# SmartWatch-V2-Power.net
KiCad netlist of a schematic drawn in Altium Designer
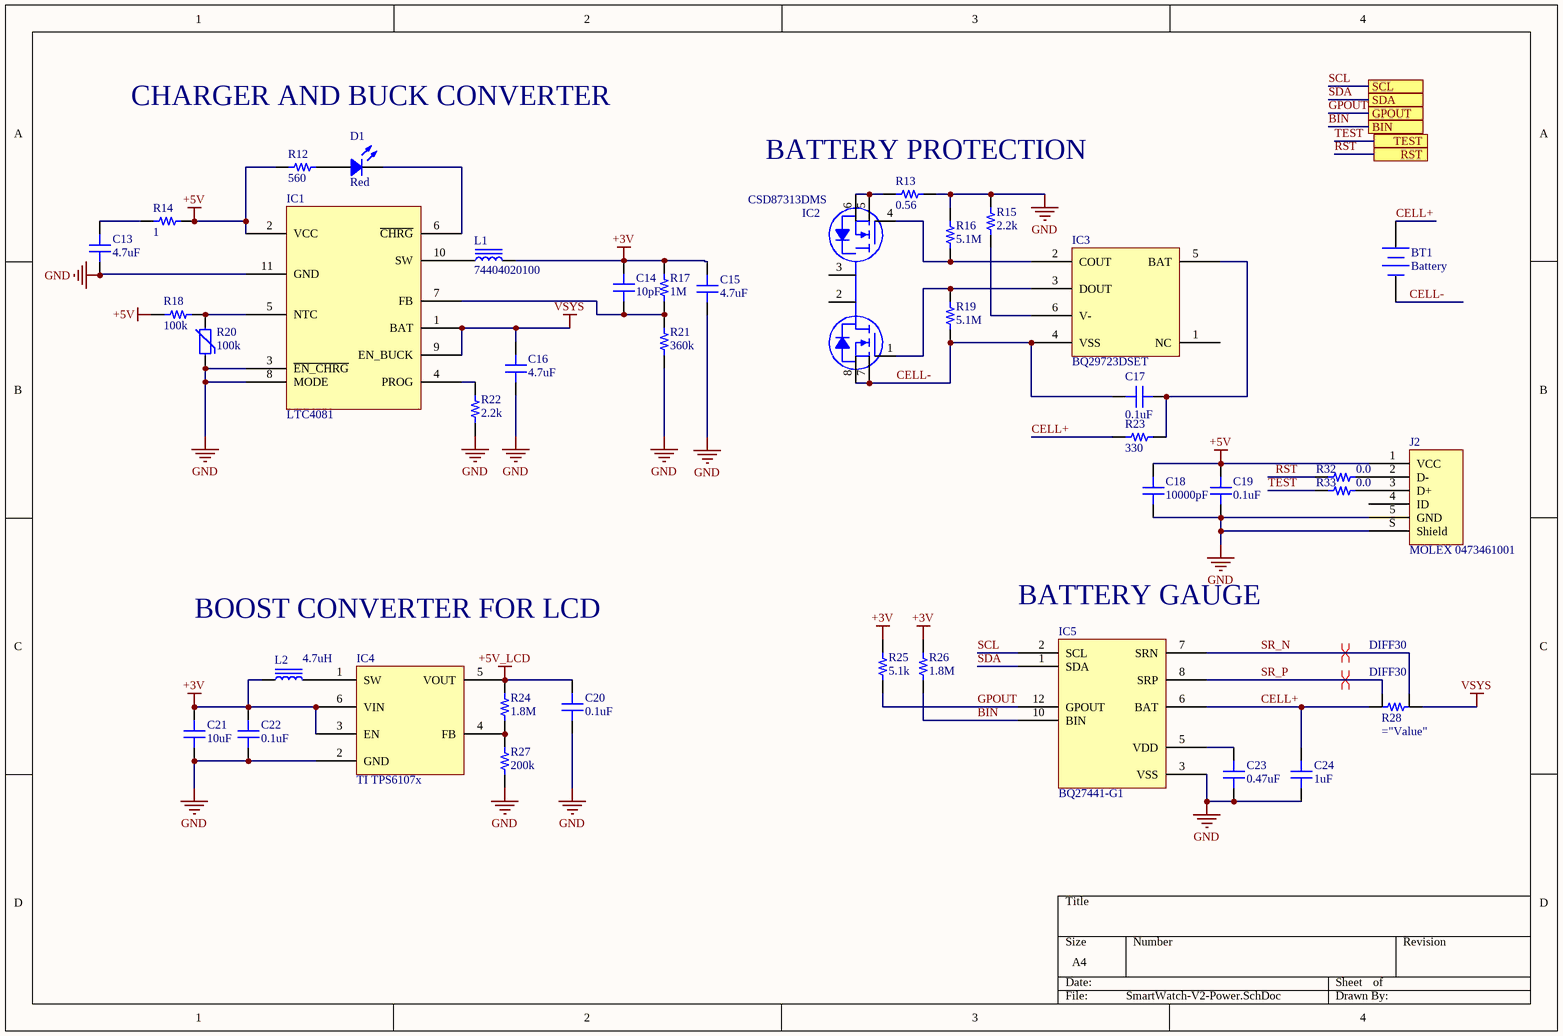
[diagram p0: SmartWatch-V2-Power.SchDoc]

(export (version "E")
  (design (tool "Eeschema 10.0.6"))
  (components
    (comp (ref "BT1")
      (value "Battery")
      (footprint "BAT-2")
      (description "Multicell Battery")
      (fields (field (name "PUBLISHER") "Altium Limited"))
      (libsource (lib "Miscellaneous Devices") (part "Battery"))
    )
    (comp (ref "C13")
      (value "4.7uF")
      (footprint "CAP 0402/1005")
      (description "CAP CER 4.7UF 4V X5R 0402")
      (fields (field (name "PART NUMBER") "CC0402MRX5R4BB475") (field (name "MANUFACTURER") "Yageo"))
      (libsource (lib "Celestial Library Database") (part "Capacitor"))
    )
    (comp (ref "C14")
      (value "10pF")
      (footprint "CAP 0402/1005")
      (description "CAP CER 10PF 50V C0G 0402")
      (fields
        (field (name "PART NUMBER") "C1005C0G1H100D050BA")
        (field (name "MANUFACTURER") "TDK Corporation")
      )
      (libsource (lib "Celestial Library Database") (part "Capacitor"))
    )
    (comp (ref "C15")
      (value "4.7uF")
      (footprint "CAP 0402/1005")
      (description "CAP CER 4.7UF 4V X5R 0402")
      (fields (field (name "PART NUMBER") "CC0402MRX5R4BB475") (field (name "MANUFACTURER") "Yageo"))
      (libsource (lib "Celestial Library Database") (part "Capacitor"))
    )
    (comp (ref "C16")
      (value "4.7uF")
      (footprint "CAP 0402/1005")
      (description "CAP CER 4.7UF 4V X5R 0402")
      (fields (field (name "PART NUMBER") "CC0402MRX5R4BB475") (field (name "MANUFACTURER") "Yageo"))
      (libsource (lib "Celestial Library Database") (part "Capacitor"))
    )
    (comp (ref "C17")
      (value "0.1uF")
      (footprint "CAP 0402/1005")
      (description "CAP CER 0.1UF 25V X7R 0402")
      (fields
        (field (name "PART NUMBER") "C1005X7R1E104K050BB")
        (field (name "MANUFACTURER") "TDK Corporation")
      )
      (libsource (lib "Celestial Library Database") (part "Capacitor"))
    )
    (comp (ref "C18")
      (value "10000pF")
      (footprint "CAP 0603/1608")
      (description "CAP CER 10000PF 100V X7R 0603")
      (fields
        (field (name "PART NUMBER") "C1608X7R2A103K080AA")
        (field (name "MANUFACTURER") "TDK Corporation")
      )
      (libsource (lib "Celestial Library Database") (part "Capacitor"))
    )
    (comp (ref "C19")
      (value "0.1uF")
      (footprint "CAP 0402/1005")
      (description "CAP CER 0.1UF 25V X7R 0402")
      (fields
        (field (name "PART NUMBER") "C1005X7R1E104K050BB")
        (field (name "MANUFACTURER") "TDK Corporation")
      )
      (libsource (lib "Celestial Library Database") (part "Capacitor"))
    )
    (comp (ref "C20")
      (value "0.1uF")
      (footprint "CAP 0402/1005")
      (description "CAP CER 0.1UF 25V X7R 0402")
      (fields
        (field (name "PART NUMBER") "C1005X7R1E104K050BB")
        (field (name "MANUFACTURER") "TDK Corporation")
      )
      (libsource (lib "Celestial Library Database") (part "Capacitor"))
    )
    (comp (ref "C21")
      (value "10uF")
      (footprint "CAP 0402/1005")
      (description "CAP CER 10UF 6.3V X5R 0402")
      (fields
        (field (name "PART NUMBER") "C1005X5R0J106M050BC")
        (field (name "MANUFACTURER") "TDK Corporation")
      )
      (libsource (lib "Celestial Library Database") (part "Capacitor"))
    )
    (comp (ref "C22")
      (value "0.1uF")
      (footprint "CAP 0402/1005")
      (description "CAP CER 0.1UF 25V X7R 0402")
      (fields
        (field (name "PART NUMBER") "C1005X7R1E104K050BB")
        (field (name "MANUFACTURER") "TDK Corporation")
      )
      (libsource (lib "Celestial Library Database") (part "Capacitor"))
    )
    (comp (ref "C23")
      (value "0.47uF")
      (footprint "CAP 0402/1005")
      (description "CAP CER 0.47UF 10V X5R 0402")
      (fields
        (field (name "PART NUMBER") "GRM155R61A474KE15D")
        (field (name "MANUFACTURER") "Murata Electronics North America")
      )
      (libsource (lib "Celestial Library Database") (part "Capacitor"))
    )
    (comp (ref "C24")
      (value "1uF")
      (footprint "CAP 0402/1005")
      (description "CAP CER 1UF 4V X7R 0402")
      (fields
        (field (name "PART NUMBER") "GRM155R70G105KA12D")
        (field (name "MANUFACTURER") "Murata Electronics North America")
      )
      (libsource (lib "Celestial Library Database") (part "Capacitor"))
    )
    (comp (ref "D1")
      (value "Red")
      (footprint "LED 0603/1608 RED")
      (description "LED RED DIFFUSED 0603 SMD")
      (fields (field (name "PART NUMBER") "5975112407F") (field (name "MANUFACTURER") "Dialight"))
      (libsource (lib "Celestial Library Database") (part "LED"))
    )
    (comp (ref "IC1")
      (value "LTC4081")
      (footprint "LT DFN-10 3mmx3mm DD")
      (description "IC BATTA CHRGR LI-ON with BUCK 10 DFN")
      (fields (field (name "MANUFACTURER") "Linear Technology"))
      (libsource (lib "Celestial Library Database") (part "LT LTC4081"))
    )
    (comp (ref "IC2")
      (value "CSD87313DMS")
      (footprint "TI WSON-8 3.3x3.3mm")
      (description "MOSFET 2 N-CHANNEL 30V 8WSON")
      (fields (field (name "MANUFACTURER") "Texas Instruments"))
      (libsource (lib "Celestial Library Database") (part "TI CSD87313DMS"))
    )
    (comp (ref "IC3")
      (value "BQ29723DSET")
      (footprint "TI WSON-6")
      (description "IC LITHIUM BATT PROTECT 6WSON")
      (fields (field (name "MANUFACTURER") "Texas Instruments"))
      (libsource (lib "Celestial Library Database") (part "TI BQ297x"))
    )
    (comp (ref "IC4")
      (value "TI TPS6107x")
      (footprint "TI SOT-23-6 DDC")
      (description "IC REG BOOST ADJ 455MA SYNC SOT6")
      (fields (field (name "MANUFACTURER") "Texas Instruments"))
      (libsource (lib "Celestial Library Database") (part "TI TPS6107x"))
    )
    (comp (ref "IC5")
      (value "BQ27441-G1")
      (footprint "TI VSON-12 2.5x4mm")
      (description "IC BATT FUEL GAUGE LI-ION 12SON")
      (fields (field (name "MANUFACTURER") "Texas Instruments"))
      (libsource (lib "Celestial Library Database") (part "TI BQ27441-G1"))
    )
    (comp (ref "J2")
      (value "MOLEX 0473461001")
      (footprint "MOLEX 0473461001")
      (description "CONN USB B SINGLE SMT HORIZ CONNECTOR")
      (fields (field (name "MANUFACTURER") "Molex"))
      (libsource (lib "Celestial Library Database") (part "USB 2.0 Type B Micro"))
    )
    (comp (ref "L1")
      (value "74404020100")
      (footprint "TDK VLS201612CX")
      (fields
        (field (name "PART NUMBER") "VLS201610CX-100M")
        (field (name "MANUFACTURER") "TDK Corporation")
        (field (name "TOLERANCE") "20%")
      )
      (libsource (lib "Celestial Library Database") (part "Inductor"))
    )
    (comp (ref "L2")
      (value "4.7uH")
      (footprint "TDK VLS201612CX")
      (description "FIXED IND 4.7UH 1.12A 252 MOHM")
      (fields (field (name "PART NUMBER") "VLS201612CX-4R7M") (field (name "MANUFACTURER") "TDK Corporation"))
      (libsource (lib "Celestial Library Database") (part "Inductor"))
    )
    (comp (ref "R12")
      (value "560")
      (footprint "RES 0402/1005")
      (description "RES SMD 560 OHM 0.1% 1/16W 0402")
      (fields
        (field (name "PART NUMBER") "ERA-2APB561X")
        (field (name "MANUFACTURER") "Panasonic Electronic Components")
      )
      (libsource (lib "Celestial Library Database") (part "Resistor"))
    )
    (comp (ref "R13")
      (value "0.56")
      (footprint "RES 0603/1608")
      (description "RES SMD 0.56 OHM 5% 1/4W 0603")
      (fields
        (field (name "PART NUMBER") "ERJ-3BQJR56V")
        (field (name "MANUFACTURER") "Panasonic Electronic Components")
      )
      (libsource (lib "Celestial Library Database") (part "Resistor"))
    )
    (comp (ref "R14")
      (value "1")
      (footprint "RES 0402/1005")
      (description "RES SMD 1 OHM 5% 1/16W 0402")
      (fields (field (name "PART NUMBER") "RC0402JR-071RL") (field (name "MANUFACTURER") "Yageo"))
      (libsource (lib "Celestial Library Database") (part "Resistor"))
    )
    (comp (ref "R15")
      (value "2.2k")
      (footprint "RES 0402/1005")
      (description "RES SMD 2.2K OHM 0.1% 1/16W 0402")
      (fields
        (field (name "PART NUMBER") "ERA-2AEB222X")
        (field (name "MANUFACTURER") "Panasonic Electronic Components")
      )
      (libsource (lib "Celestial Library Database") (part "Resistor"))
    )
    (comp (ref "R16")
      (value "5.1M")
      (footprint "RES 0402/1005")
      (description "RES SMD 5.1M OHM 5% 1/10W 0402")
      (fields
        (field (name "PART NUMBER") "ERJ-2GEJ515X")
        (field (name "MANUFACTURER") "Panasonic Electronic Components")
      )
      (libsource (lib "Celestial Library Database") (part "Resistor"))
    )
    (comp (ref "R17")
      (value "1M")
      (footprint "RES 0402/1005")
      (description "RES SMD 1M OHM 5% 1/10W 0402")
      (fields
        (field (name "PART NUMBER") "ERJ-2GEJ105X")
        (field (name "MANUFACTURER") "Panasonic Electronic Components")
      )
      (libsource (lib "Celestial Library Database") (part "Resistor"))
    )
    (comp (ref "R18")
      (value "100k")
      (footprint "RES 0402/1005")
      (description "RES SMD 100K OHM 0.5% 1/16W 0402")
      (fields
        (field (name "PART NUMBER") "ERA-2AED104X")
        (field (name "MANUFACTURER") "Panasonic Electronic Components")
      )
      (libsource (lib "Celestial Library Database") (part "Resistor"))
    )
    (comp (ref "R19")
      (value "5.1M")
      (footprint "RES 0402/1005")
      (description "RES SMD 5.1M OHM 5% 1/10W 0402")
      (fields
        (field (name "PART NUMBER") "ERJ-2GEJ515X")
        (field (name "MANUFACTURER") "Panasonic Electronic Components")
      )
      (libsource (lib "Celestial Library Database") (part "Resistor"))
    )
    (comp (ref "R20")
      (value "~")
      (footprint "FER 0603/1608")
      (description "THERMISTOR NTC 100K OHM 5% 0603")
      (fields
        (field (name "PART NUMBER") "ABNTC-0603-104J-4250F-T")
        (field (name "RESISTANCE IN OHMS @ 25C") "100k")
        (field (name "MANUFACTURER") "Abracon LLC")
      )
      (libsource (lib "Celestial Library Database") (part "Thermistor"))
    )
    (comp (ref "R21")
      (value "360k")
      (footprint "RES 0402/1005")
      (description "RES SMD 360K OHM 5% 1/10W 0402")
      (fields
        (field (name "PART NUMBER") "ERJ-2GEJ364X")
        (field (name "MANUFACTURER") "Panasonic Electronic Components")
      )
      (libsource (lib "Celestial Library Database") (part "Resistor"))
    )
    (comp (ref "R22")
      (value "2.2k")
      (footprint "RES 0402/1005")
      (description "RES SMD 2.2K OHM 0.1% 1/16W 0402")
      (fields
        (field (name "PART NUMBER") "ERA-2AEB222X")
        (field (name "MANUFACTURER") "Panasonic Electronic Components")
      )
      (libsource (lib "Celestial Library Database") (part "Resistor"))
    )
    (comp (ref "R23")
      (value "330")
      (footprint "RES 0402/1005")
      (description "RES SMD 330 OHM 0.5% 1/16W 0402")
      (fields
        (field (name "PART NUMBER") "ERA-2AED331X")
        (field (name "MANUFACTURER") "Panasonic Electronic Components")
      )
      (libsource (lib "Celestial Library Database") (part "Resistor"))
    )
    (comp (ref "R24")
      (value "1.8M")
      (footprint "RES 0603/1608")
      (description "RES SMD 1.8M OHM 5% 1/10W 0603")
      (fields
        (field (name "PART NUMBER") "ERJ-3GEYJ185V")
        (field (name "MANUFACTURER") "Panasonic Electronic Components")
      )
      (libsource (lib "Celestial Library Database") (part "Resistor"))
    )
    (comp (ref "R25")
      (value "5.1k")
      (footprint "RES 0402/1005")
      (description "RES SMD 5.1K OHM 0.5% 1/16W 0402")
      (fields
        (field (name "PART NUMBER") "ERA-2AED512X")
        (field (name "MANUFACTURER") "Panasonic Electronic Components")
      )
      (libsource (lib "Celestial Library Database") (part "Resistor"))
    )
    (comp (ref "R26")
      (value "1.8M")
      (footprint "RES 0402/1005")
      (description "RES SMD 1.8M OHM 5% 1/10W 0402")
      (fields
        (field (name "PART NUMBER") "ERJ-2GEJ185X")
        (field (name "MANUFACTURER") "Panasonic Electronic Components")
      )
      (libsource (lib "Celestial Library Database") (part "Resistor"))
    )
    (comp (ref "R27")
      (value "200k")
      (footprint "RES 0603/1608")
      (description "RES SMD 200K OHM 0.1% 1/10W 0603")
      (fields
        (field (name "PART NUMBER") "ERA-3AEB204V")
        (field (name "MANUFACTURER") "Panasonic Electronic Components")
      )
      (libsource (lib "Celestial Library Database") (part "Resistor"))
    )
    (comp (ref "R28")
      (value "~")
      (footprint "Current Res CSR1206")
      (description "1206")
      (fields (field (name "PART NUMBER") "Current Resistor"))
      (libsource (lib "Celestial Library Database") (part "Current Resistor"))
    )
    (comp (ref "R32")
      (value "0.0")
      (footprint "RES 0603/1608")
      (description "RES SMD 0.0OHM JUMPER 1/10W 0603")
      (fields
        (field (name "PART NUMBER") "ERJ-3GEY0R00V")
        (field (name "MANUFACTURER") "Panasonic Electronic Components")
      )
      (libsource (lib "Celestial Library Database") (part "Resistor"))
    )
    (comp (ref "R33")
      (value "0.0")
      (footprint "RES 0603/1608")
      (description "RES SMD 0.0OHM JUMPER 1/10W 0603")
      (fields
        (field (name "PART NUMBER") "ERJ-3GEY0R00V")
        (field (name "MANUFACTURER") "Panasonic Electronic Components")
      )
      (libsource (lib "Celestial Library Database") (part "Resistor"))
    )
  )
  (nets
    (net (code "1") (name "+3V") (class "Default")
      (node (ref "C14") (pin "2") (pinfunction "2_2") (pintype "passive"))
      (node (ref "C15") (pin "2") (pinfunction "2_2") (pintype "passive"))
      (node (ref "C21") (pin "2") (pinfunction "2_2") (pintype "passive"))
      (node (ref "C22") (pin "2") (pinfunction "2_2") (pintype "passive"))
      (node (ref "IC4") (pin "3") (pinfunction "EN_3") (pintype "passive"))
      (node (ref "IC4") (pin "6") (pinfunction "VIN_6") (pintype "passive"))
      (node (ref "L1") (pin "2") (pinfunction "2_2") (pintype "passive"))
      (node (ref "L2") (pin "1") (pinfunction "1_1") (pintype "passive"))
      (node (ref "R17") (pin "2") (pinfunction "2_2") (pintype "passive"))
      (node (ref "R25") (pin "2") (pinfunction "2_2") (pintype "passive"))
      (node (ref "R26") (pin "2") (pinfunction "2_2") (pintype "passive"))
    )
    (net (code "2") (name "+5V") (class "Default")
      (node (ref "C18") (pin "2") (pinfunction "2_2") (pintype "passive"))
      (node (ref "C19") (pin "2") (pinfunction "2_2") (pintype "passive"))
      (node (ref "IC1") (pin "2") (pinfunction "VCC_2") (pintype "passive"))
      (node (ref "J2") (pin "1") (pinfunction "VCC_1") (pintype "passive"))
      (node (ref "R12") (pin "1") (pinfunction "1_1") (pintype "passive"))
      (node (ref "R14") (pin "2") (pinfunction "2_2") (pintype "passive"))
      (node (ref "R18") (pin "1") (pinfunction "1_1") (pintype "passive"))
    )
    (net (code "3") (name "+5V_LCD") (class "Default")
      (node (ref "C20") (pin "2") (pinfunction "2_2") (pintype "passive"))
      (node (ref "IC4") (pin "5") (pinfunction "VOUT_5") (pintype "passive"))
      (node (ref "R24") (pin "2") (pinfunction "2_2") (pintype "passive"))
    )
    (net (code "4") (name "/BIN") (class "Default")
      (node (ref "IC5") (pin "10") (pinfunction "BIN_10") (pintype "passive"))
      (node (ref "R26") (pin "1") (pinfunction "1_1") (pintype "passive"))
    )
    (net (code "5") (name "/CELL+") (class "Default")
      (node (ref "BT1") (pin "1") (pinfunction "+_1") (pintype "passive"))
      (node (ref "C24") (pin "2") (pinfunction "2_2") (pintype "passive"))
      (node (ref "IC5") (pin "6") (pinfunction "BAT_6") (pintype "passive"))
      (node (ref "R23") (pin "1") (pinfunction "1_1") (pintype "passive"))
      (node (ref "R28") (pin "1") (pinfunction "1_1") (pintype "passive"))
    )
    (net (code "6") (name "/CELL-") (class "Default")
      (node (ref "BT1") (pin "2") (pinfunction "-_2") (pintype "passive"))
      (node (ref "C17") (pin "1") (pinfunction "1_1") (pintype "passive"))
      (node (ref "IC2") (pin "7") (pinfunction "S1_7") (pintype "passive"))
      (node (ref "IC2") (pin "8") (pinfunction "S2_8") (pintype "passive"))
      (node (ref "IC3") (pin "4") (pinfunction "VSS_4") (pintype "passive"))
      (node (ref "R19") (pin "1") (pinfunction "1_1") (pintype "passive"))
    )
    (net (code "7") (name "/GPOUT") (class "Default")
      (node (ref "IC5") (pin "12") (pinfunction "GPOUT_12") (pintype "passive"))
      (node (ref "R25") (pin "1") (pinfunction "1_1") (pintype "passive"))
    )
    (net (code "8") (name "/RST") (class "Default")
      (node (ref "R32") (pin "2") (pinfunction "2_2") (pintype "passive"))
    )
    (net (code "9") (name "/SCL") (class "Default")
      (node (ref "IC5") (pin "2") (pinfunction "SCL_2") (pintype "passive"))
    )
    (net (code "10") (name "/SDA") (class "Default")
      (node (ref "IC5") (pin "1") (pinfunction "SDA_1") (pintype "passive"))
    )
    (net (code "11") (name "/SR_N") (class "Default")
      (node (ref "IC5") (pin "7") (pinfunction "SRN_7") (pintype "passive"))
      (node (ref "R28") (pin "4") (pinfunction "4_4") (pintype "passive"))
    )
    (net (code "12") (name "/SR_P") (class "Default")
      (node (ref "IC5") (pin "8") (pinfunction "SRP_8") (pintype "passive"))
      (node (ref "R28") (pin "3") (pinfunction "3_3") (pintype "passive"))
    )
    (net (code "13") (name "/TEST") (class "Default")
      (node (ref "R33") (pin "2") (pinfunction "2_2") (pintype "passive"))
    )
    (net (code "14") (name "GND") (class "Default")
      (node (ref "C13") (pin "1") (pinfunction "1_1") (pintype "passive"))
      (node (ref "C15") (pin "1") (pinfunction "1_1") (pintype "passive"))
      (node (ref "C16") (pin "1") (pinfunction "1_1") (pintype "passive"))
      (node (ref "C18") (pin "1") (pinfunction "1_1") (pintype "passive"))
      (node (ref "C19") (pin "1") (pinfunction "1_1") (pintype "passive"))
      (node (ref "C20") (pin "1") (pinfunction "1_1") (pintype "passive"))
      (node (ref "C21") (pin "1") (pinfunction "1_1") (pintype "passive"))
      (node (ref "C22") (pin "1") (pinfunction "1_1") (pintype "passive"))
      (node (ref "C23") (pin "1") (pinfunction "1_1") (pintype "passive"))
      (node (ref "C24") (pin "1") (pinfunction "1_1") (pintype "passive"))
      (node (ref "IC1") (pin "11") (pinfunction "GND_11") (pintype "passive"))
      (node (ref "IC1") (pin "3") (pinfunction "~{EN_CHRG}_3") (pintype "passive"))
      (node (ref "IC1") (pin "8") (pinfunction "MODE_8") (pintype "passive"))
      (node (ref "IC4") (pin "2") (pinfunction "GND_2") (pintype "passive"))
      (node (ref "IC5") (pin "3") (pinfunction "VSS_3") (pintype "passive"))
      (node (ref "J2") (pin "5") (pinfunction "GND_5") (pintype "passive"))
      (node (ref "J2") (pin "S") (pinfunction "Shield_S") (pintype "passive"))
      (node (ref "R13") (pin "2") (pinfunction "2_2") (pintype "passive"))
      (node (ref "R15") (pin "2") (pinfunction "2_2") (pintype "passive"))
      (node (ref "R16") (pin "2") (pinfunction "2_2") (pintype "passive"))
      (node (ref "R20") (pin "1") (pinfunction "1_1") (pintype "passive"))
      (node (ref "R21") (pin "1") (pinfunction "1_1") (pintype "passive"))
      (node (ref "R22") (pin "1") (pinfunction "1_1") (pintype "passive"))
      (node (ref "R27") (pin "1") (pinfunction "1_1") (pintype "passive"))
    )
    (net (code "15") (name "Net-(C13-Pad2)") (class "Default")
      (node (ref "C13") (pin "2") (pinfunction "2_2") (pintype "passive"))
      (node (ref "R14") (pin "1") (pinfunction "1_1") (pintype "passive"))
    )
    (net (code "16") (name "Net-(D1-Pad1)") (class "Default")
      (node (ref "D1") (pin "1") (pinfunction "1_1") (pintype "passive"))
      (node (ref "R12") (pin "2") (pinfunction "2_2") (pintype "passive"))
    )
    (net (code "17") (name "Net-(IC1-FB)") (class "Default")
      (node (ref "C14") (pin "1") (pinfunction "1_1") (pintype "passive"))
      (node (ref "IC1") (pin "7") (pinfunction "FB_7") (pintype "passive"))
      (node (ref "R17") (pin "1") (pinfunction "1_1") (pintype "passive"))
      (node (ref "R21") (pin "2") (pinfunction "2_2") (pintype "passive"))
    )
    (net (code "18") (name "Net-(IC1-NTC)") (class "Default")
      (node (ref "IC1") (pin "5") (pinfunction "NTC_5") (pintype "passive"))
      (node (ref "R18") (pin "2") (pinfunction "2_2") (pintype "passive"))
      (node (ref "R20") (pin "2") (pinfunction "2_2") (pintype "passive"))
    )
    (net (code "19") (name "Net-(IC1-PROG)") (class "Default")
      (node (ref "IC1") (pin "4") (pinfunction "PROG_4") (pintype "passive"))
      (node (ref "R22") (pin "2") (pinfunction "2_2") (pintype "passive"))
    )
    (net (code "20") (name "Net-(IC1-SW)") (class "Default")
      (node (ref "IC1") (pin "10") (pinfunction "SW_10") (pintype "passive"))
      (node (ref "L1") (pin "1") (pinfunction "1_1") (pintype "passive"))
    )
    (net (code "21") (name "Net-(IC1-~{CHRG})") (class "Default")
      (node (ref "D1") (pin "2") (pinfunction "2_2") (pintype "passive"))
      (node (ref "IC1") (pin "6") (pinfunction "~{CHRG}_6") (pintype "passive"))
    )
    (net (code "22") (name "Net-(IC2-G1)") (class "Default")
      (node (ref "IC2") (pin "1") (pinfunction "G1_1") (pintype "passive"))
      (node (ref "IC3") (pin "3") (pinfunction "DOUT_3") (pintype "passive"))
      (node (ref "R19") (pin "2") (pinfunction "2_2") (pintype "passive"))
    )
    (net (code "23") (name "Net-(IC2-G2)") (class "Default")
      (node (ref "IC2") (pin "4") (pinfunction "G2_4") (pintype "passive"))
      (node (ref "IC3") (pin "2") (pinfunction "COUT_2") (pintype "passive"))
      (node (ref "R16") (pin "1") (pinfunction "1_1") (pintype "passive"))
    )
    (net (code "24") (name "Net-(IC2-S3)") (class "Default")
      (node (ref "IC2") (pin "5") (pinfunction "S2_5") (pintype "passive"))
      (node (ref "IC2") (pin "6") (pinfunction "S3_6") (pintype "passive"))
      (node (ref "R13") (pin "1") (pinfunction "1_1") (pintype "passive"))
    )
    (net (code "25") (name "Net-(IC3-BAT)") (class "Default")
      (node (ref "C17") (pin "2") (pinfunction "2_2") (pintype "passive"))
      (node (ref "IC3") (pin "5") (pinfunction "BAT_5") (pintype "passive"))
      (node (ref "R23") (pin "2") (pinfunction "2_2") (pintype "passive"))
    )
    (net (code "26") (name "Net-(IC3-V-)") (class "Default")
      (node (ref "IC3") (pin "6") (pinfunction "V-_6") (pintype "passive"))
      (node (ref "R15") (pin "1") (pinfunction "1_1") (pintype "passive"))
    )
    (net (code "27") (name "Net-(IC4-FB)") (class "Default")
      (node (ref "IC4") (pin "4") (pinfunction "FB_4") (pintype "passive"))
      (node (ref "R24") (pin "1") (pinfunction "1_1") (pintype "passive"))
      (node (ref "R27") (pin "2") (pinfunction "2_2") (pintype "passive"))
    )
    (net (code "28") (name "Net-(IC4-SW)") (class "Default")
      (node (ref "IC4") (pin "1") (pinfunction "SW_1") (pintype "passive"))
      (node (ref "L2") (pin "2") (pinfunction "2_2") (pintype "passive"))
    )
    (net (code "29") (name "Net-(IC5-VDD)") (class "Default")
      (node (ref "C23") (pin "2") (pinfunction "2_2") (pintype "passive"))
      (node (ref "IC5") (pin "5") (pinfunction "VDD_5") (pintype "passive"))
    )
    (net (code "30") (name "Net-(J2-D+)") (class "Default")
      (node (ref "J2") (pin "3") (pinfunction "D+_3") (pintype "passive"))
      (node (ref "R33") (pin "1") (pinfunction "1_1") (pintype "passive"))
    )
    (net (code "31") (name "Net-(J2-D-)") (class "Default")
      (node (ref "J2") (pin "2") (pinfunction "D-_2") (pintype "passive"))
      (node (ref "R32") (pin "1") (pinfunction "1_1") (pintype "passive"))
    )
    (net (code "32") (name "VSYS") (class "Default")
      (node (ref "C16") (pin "2") (pinfunction "2_2") (pintype "passive"))
      (node (ref "IC1") (pin "1") (pinfunction "BAT_1") (pintype "passive"))
      (node (ref "IC1") (pin "9") (pinfunction "EN_BUCK_9") (pintype "passive"))
      (node (ref "R28") (pin "2") (pinfunction "2_2") (pintype "passive"))
    )
    (net (code "33") (name "unconnected-(IC2-D-Pad2)") (class "Default")
      (node (ref "IC2") (pin "2") (pinfunction "D_2") (pintype "passive"))
    )
    (net (code "34") (name "unconnected-(IC2-D-Pad3)") (class "Default")
      (node (ref "IC2") (pin "3") (pinfunction "D_3") (pintype "passive"))
    )
    (net (code "35") (name "unconnected-(IC3-NC-Pad1)") (class "Default")
      (node (ref "IC3") (pin "1") (pinfunction "NC_1") (pintype "passive"))
    )
    (net (code "36") (name "unconnected-(IC5-NC-Pad4)") (class "Default")
      (node (ref "IC5") (pin "4") (pinfunction "NC_4") (pintype "passive"))
    )
    (net (code "37") (name "unconnected-(IC5-NC-Pad9)") (class "Default")
      (node (ref "IC5") (pin "9") (pinfunction "NC_9") (pintype "passive"))
    )
    (net (code "38") (name "unconnected-(IC5-NC-Pad11)") (class "Default")
      (node (ref "IC5") (pin "11") (pinfunction "NC_11") (pintype "passive"))
    )
    (net (code "39") (name "unconnected-(J2-ID-Pad4)") (class "Default")
      (node (ref "J2") (pin "4") (pinfunction "ID_4") (pintype "passive"))
    )
  )
)
